# top_schem_rev10_3.net
KiCad netlist of a schematic drawn in Altium Designer
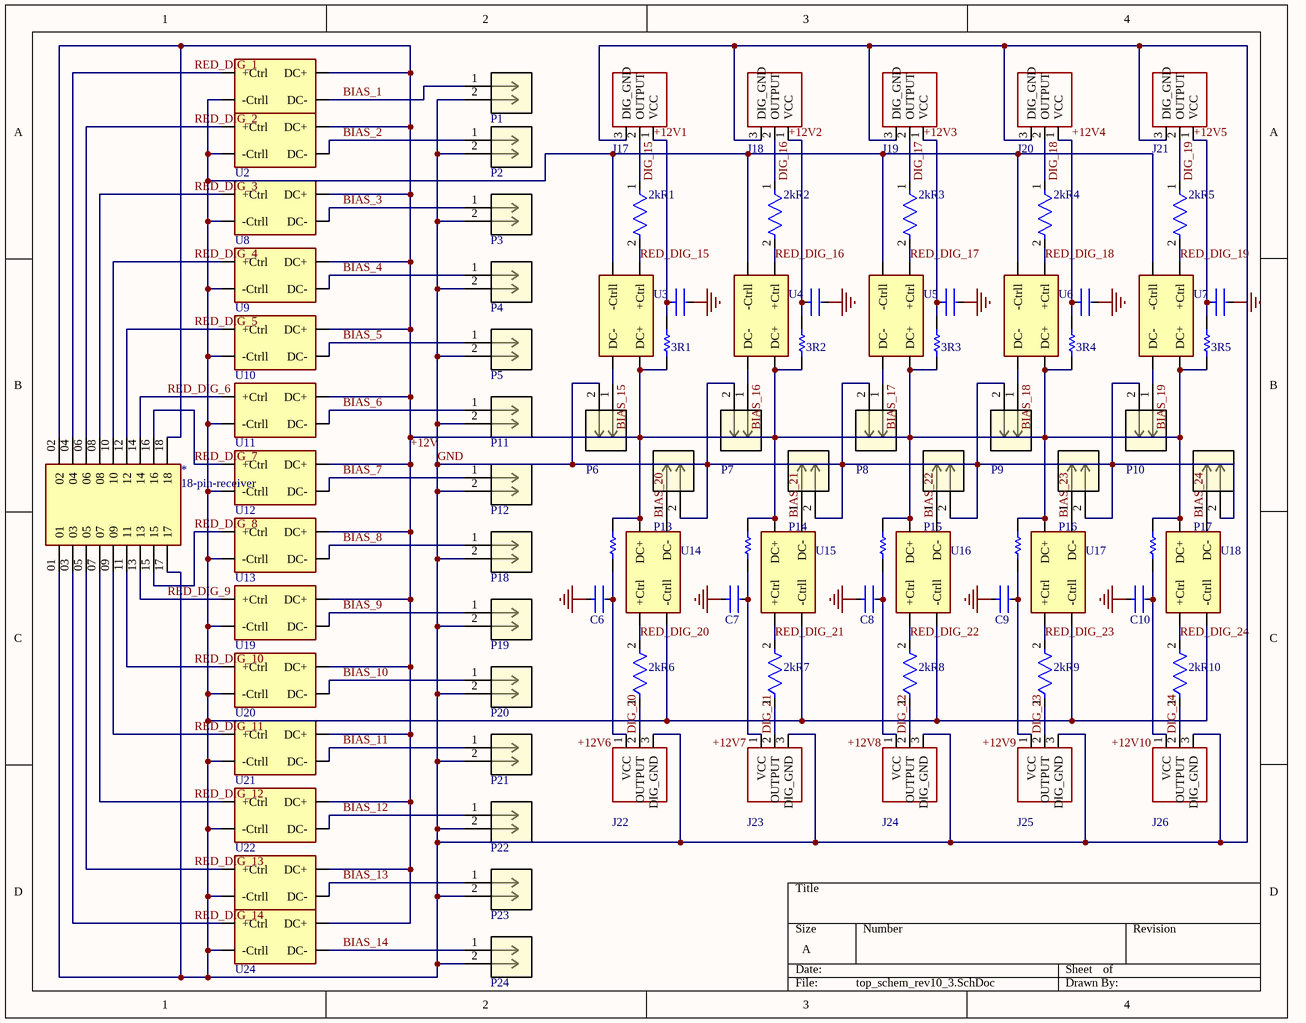
[diagram p0: top_schem_rev10_3.SchDoc]

(export (version "E")
  (design (tool "Eeschema 10.0.6"))
  (components
    (comp (ref "*")
      (value "18-pin-receiver")
      (footprint "18-pin-receiver")
      (libsource (lib "top_schlib") (part "18-pin-receiver"))
    )
    (comp (ref "2kR1")
      (value "CRCW06031K80FKEA")
      (footprint "2kOhm")
      (description "Res Thick Film 0603 1.8K Ohm 1% 1/10W ±100ppm/°C Molded SMD Paper T/R")
      (fields (field (name "MANUFACTURER") "Vishay") (field (name "TOLERANCE") "1%"))
      (libsource (lib "ps_schlib") (part "CRCW06031K80FKEA"))
    )
    (comp (ref "2kR2")
      (value "CRCW06031K80FKEA")
      (footprint "2kOhm")
      (description "Res Thick Film 0603 1.8K Ohm 1% 1/10W ±100ppm/°C Molded SMD Paper T/R")
      (fields (field (name "MANUFACTURER") "Vishay") (field (name "TOLERANCE") "1%"))
      (libsource (lib "ps_schlib") (part "CRCW06031K80FKEA"))
    )
    (comp (ref "2kR3")
      (value "CRCW06031K80FKEA")
      (footprint "2kOhm")
      (description "Res Thick Film 0603 1.8K Ohm 1% 1/10W ±100ppm/°C Molded SMD Paper T/R")
      (fields (field (name "MANUFACTURER") "Vishay") (field (name "TOLERANCE") "1%"))
      (libsource (lib "ps_schlib") (part "CRCW06031K80FKEA"))
    )
    (comp (ref "2kR4")
      (value "CRCW06031K80FKEA")
      (footprint "2kOhm")
      (description "Res Thick Film 0603 1.8K Ohm 1% 1/10W ±100ppm/°C Molded SMD Paper T/R")
      (fields (field (name "MANUFACTURER") "Vishay") (field (name "TOLERANCE") "1%"))
      (libsource (lib "ps_schlib") (part "CRCW06031K80FKEA"))
    )
    (comp (ref "2kR5")
      (value "CRCW06031K80FKEA")
      (footprint "2kOhm")
      (description "Res Thick Film 0603 1.8K Ohm 1% 1/10W ±100ppm/°C Molded SMD Paper T/R")
      (fields (field (name "MANUFACTURER") "Vishay") (field (name "TOLERANCE") "1%"))
      (libsource (lib "ps_schlib") (part "CRCW06031K80FKEA"))
    )
    (comp (ref "2kR6")
      (value "CRCW06031K80FKEA")
      (footprint "2kOhm")
      (description "Res Thick Film 0603 1.8K Ohm 1% 1/10W ±100ppm/°C Molded SMD Paper T/R")
      (fields (field (name "MANUFACTURER") "Vishay") (field (name "TOLERANCE") "1%"))
      (libsource (lib "ps_schlib") (part "CRCW06031K80FKEA"))
    )
    (comp (ref "2kR7")
      (value "CRCW06031K80FKEA")
      (footprint "2kOhm")
      (description "Res Thick Film 0603 1.8K Ohm 1% 1/10W ±100ppm/°C Molded SMD Paper T/R")
      (fields (field (name "MANUFACTURER") "Vishay") (field (name "TOLERANCE") "1%"))
      (libsource (lib "ps_schlib") (part "CRCW06031K80FKEA"))
    )
    (comp (ref "2kR8")
      (value "CRCW06031K80FKEA")
      (footprint "2kOhm")
      (description "Res Thick Film 0603 1.8K Ohm 1% 1/10W ±100ppm/°C Molded SMD Paper T/R")
      (fields (field (name "MANUFACTURER") "Vishay") (field (name "TOLERANCE") "1%"))
      (libsource (lib "ps_schlib") (part "CRCW06031K80FKEA"))
    )
    (comp (ref "2kR9")
      (value "CRCW06031K80FKEA")
      (footprint "2kOhm")
      (description "Res Thick Film 0603 1.8K Ohm 1% 1/10W ±100ppm/°C Molded SMD Paper T/R")
      (fields (field (name "MANUFACTURER") "Vishay") (field (name "TOLERANCE") "1%"))
      (libsource (lib "ps_schlib") (part "CRCW06031K80FKEA"))
    )
    (comp (ref "2kR10")
      (value "CRCW06031K80FKEA")
      (footprint "2kOhm")
      (description "Res Thick Film 0603 1.8K Ohm 1% 1/10W ±100ppm/°C Molded SMD Paper T/R")
      (fields (field (name "MANUFACTURER") "Vishay") (field (name "TOLERANCE") "1%"))
      (libsource (lib "ps_schlib") (part "CRCW06031K80FKEA"))
    )
    (comp (ref "3R1")
      (value "ERJ-2BQJR30X")
      (footprint "03 Ohm")
      (description "RES 0.3 OHM 5% 1/6W 0402")
      (fields (field (name "MANUFACTURER") "Panasonic") (field (name "TOLERANCE") "5%"))
      (libsource (lib "ps_schlib") (part "ERJ-2BQJR30X"))
    )
    (comp (ref "3R2")
      (value "ERJ-2BQJR30X")
      (footprint "03 Ohm")
      (description "RES 0.3 OHM 5% 1/6W 0402")
      (fields (field (name "MANUFACTURER") "Panasonic") (field (name "TOLERANCE") "5%"))
      (libsource (lib "ps_schlib") (part "ERJ-2BQJR30X"))
    )
    (comp (ref "3R3")
      (value "ERJ-2BQJR30X")
      (footprint "03 Ohm")
      (description "RES 0.3 OHM 5% 1/6W 0402")
      (fields (field (name "MANUFACTURER") "Panasonic") (field (name "TOLERANCE") "5%"))
      (libsource (lib "ps_schlib") (part "ERJ-2BQJR30X"))
    )
    (comp (ref "3R4")
      (value "ERJ-2BQJR30X")
      (footprint "03 Ohm")
      (description "RES 0.3 OHM 5% 1/6W 0402")
      (fields (field (name "MANUFACTURER") "Panasonic") (field (name "TOLERANCE") "5%"))
      (libsource (lib "ps_schlib") (part "ERJ-2BQJR30X"))
    )
    (comp (ref "3R5")
      (value "ERJ-2BQJR30X")
      (footprint "03 Ohm")
      (description "RES 0.3 OHM 5% 1/6W 0402")
      (fields (field (name "MANUFACTURER") "Panasonic") (field (name "TOLERANCE") "5%"))
      (libsource (lib "ps_schlib") (part "ERJ-2BQJR30X"))
    )
    (comp (ref "3R6")
      (value "ERJ-2BQJR30X")
      (footprint "03 Ohm")
      (description "RES 0.3 OHM 5% 1/6W 0402")
      (fields (field (name "MANUFACTURER") "Panasonic") (field (name "TOLERANCE") "5%"))
      (libsource (lib "ps_schlib") (part "ERJ-2BQJR30X"))
    )
    (comp (ref "3R7")
      (value "ERJ-2BQJR30X")
      (footprint "03 Ohm")
      (description "RES 0.3 OHM 5% 1/6W 0402")
      (fields (field (name "MANUFACTURER") "Panasonic") (field (name "TOLERANCE") "5%"))
      (libsource (lib "ps_schlib") (part "ERJ-2BQJR30X"))
    )
    (comp (ref "3R8")
      (value "ERJ-2BQJR30X")
      (footprint "03 Ohm")
      (description "RES 0.3 OHM 5% 1/6W 0402")
      (fields (field (name "MANUFACTURER") "Panasonic") (field (name "TOLERANCE") "5%"))
      (libsource (lib "ps_schlib") (part "ERJ-2BQJR30X"))
    )
    (comp (ref "3R9")
      (value "ERJ-2BQJR30X")
      (footprint "03 Ohm")
      (description "RES 0.3 OHM 5% 1/6W 0402")
      (fields (field (name "MANUFACTURER") "Panasonic") (field (name "TOLERANCE") "5%"))
      (libsource (lib "ps_schlib") (part "ERJ-2BQJR30X"))
    )
    (comp (ref "3R10")
      (value "ERJ-2BQJR30X")
      (footprint "03 Ohm")
      (description "RES 0.3 OHM 5% 1/6W 0402")
      (fields (field (name "MANUFACTURER") "Panasonic") (field (name "TOLERANCE") "5%"))
      (libsource (lib "ps_schlib") (part "ERJ-2BQJR30X"))
    )
    (comp (ref "C1")
      (value "C0805C104K5RACTU")
      (footprint "100nF")
      (description "Cap Ceramic 0.1uF 50V X7R 10% SMD 2.0 x 1.2 mm 125 C Paper T/R")
      (fields (field (name "MANUFACTURER") "KEMET") (field (name "TOLERANCE") "10%"))
      (libsource (lib "ps_schlib") (part "C0805C104K5RACTU"))
    )
    (comp (ref "C2")
      (value "C0805C104K5RACTU")
      (footprint "100nF")
      (description "Cap Ceramic 0.1uF 50V X7R 10% SMD 2.0 x 1.2 mm 125 C Paper T/R")
      (fields (field (name "MANUFACTURER") "KEMET") (field (name "TOLERANCE") "10%"))
      (libsource (lib "ps_schlib") (part "C0805C104K5RACTU"))
    )
    (comp (ref "C3")
      (value "C0805C104K5RACTU")
      (footprint "100nF")
      (description "Cap Ceramic 0.1uF 50V X7R 10% SMD 2.0 x 1.2 mm 125 C Paper T/R")
      (fields (field (name "MANUFACTURER") "KEMET") (field (name "TOLERANCE") "10%"))
      (libsource (lib "ps_schlib") (part "C0805C104K5RACTU"))
    )
    (comp (ref "C4")
      (value "C0805C104K5RACTU")
      (footprint "100nF")
      (description "Cap Ceramic 0.1uF 50V X7R 10% SMD 2.0 x 1.2 mm 125 C Paper T/R")
      (fields (field (name "MANUFACTURER") "KEMET") (field (name "TOLERANCE") "10%"))
      (libsource (lib "ps_schlib") (part "C0805C104K5RACTU"))
    )
    (comp (ref "C5")
      (value "C0805C104K5RACTU")
      (footprint "100nF")
      (description "Cap Ceramic 0.1uF 50V X7R 10% SMD 2.0 x 1.2 mm 125 C Paper T/R")
      (fields (field (name "MANUFACTURER") "KEMET") (field (name "TOLERANCE") "10%"))
      (libsource (lib "ps_schlib") (part "C0805C104K5RACTU"))
    )
    (comp (ref "C6")
      (value "C0805C104K5RACTU")
      (footprint "100nF")
      (description "Cap Ceramic 0.1uF 50V X7R 10% SMD 2.0 x 1.2 mm 125 C Paper T/R")
      (fields (field (name "MANUFACTURER") "KEMET") (field (name "TOLERANCE") "10%"))
      (libsource (lib "ps_schlib") (part "C0805C104K5RACTU"))
    )
    (comp (ref "C7")
      (value "C0805C104K5RACTU")
      (footprint "100nF")
      (description "Cap Ceramic 0.1uF 50V X7R 10% SMD 2.0 x 1.2 mm 125 C Paper T/R")
      (fields (field (name "MANUFACTURER") "KEMET") (field (name "TOLERANCE") "10%"))
      (libsource (lib "ps_schlib") (part "C0805C104K5RACTU"))
    )
    (comp (ref "C8")
      (value "C0805C104K5RACTU")
      (footprint "100nF")
      (description "Cap Ceramic 0.1uF 50V X7R 10% SMD 2.0 x 1.2 mm 125 C Paper T/R")
      (fields (field (name "MANUFACTURER") "KEMET") (field (name "TOLERANCE") "10%"))
      (libsource (lib "ps_schlib") (part "C0805C104K5RACTU"))
    )
    (comp (ref "C9")
      (value "C0805C104K5RACTU")
      (footprint "100nF")
      (description "Cap Ceramic 0.1uF 50V X7R 10% SMD 2.0 x 1.2 mm 125 C Paper T/R")
      (fields (field (name "MANUFACTURER") "KEMET") (field (name "TOLERANCE") "10%"))
      (libsource (lib "ps_schlib") (part "C0805C104K5RACTU"))
    )
    (comp (ref "C10")
      (value "C0805C104K5RACTU")
      (footprint "100nF")
      (description "Cap Ceramic 0.1uF 50V X7R 10% SMD 2.0 x 1.2 mm 125 C Paper T/R")
      (fields (field (name "MANUFACTURER") "KEMET") (field (name "TOLERANCE") "10%"))
      (libsource (lib "ps_schlib") (part "C0805C104K5RACTU"))
    )
    (comp (ref "J17")
      (value "IF-D95T")
      (footprint "IF-D95")
      (description "DETECTOR PHOTOLOGIC TTL/CMOS")
      (fields (field (name "MANUFACTURER") "Industrial Fiber Optics"))
      (libsource (lib "ps_schlib") (part "IF-D95T"))
    )
    (comp (ref "J18")
      (value "IF-D95T")
      (footprint "IF-D95")
      (description "DETECTOR PHOTOLOGIC TTL/CMOS")
      (fields (field (name "MANUFACTURER") "Industrial Fiber Optics"))
      (libsource (lib "ps_schlib") (part "IF-D95T"))
    )
    (comp (ref "J19")
      (value "IF-D95T")
      (footprint "IF-D95")
      (description "DETECTOR PHOTOLOGIC TTL/CMOS")
      (fields (field (name "MANUFACTURER") "Industrial Fiber Optics"))
      (libsource (lib "ps_schlib") (part "IF-D95T"))
    )
    (comp (ref "J20")
      (value "IF-D95T")
      (footprint "IF-D95")
      (description "DETECTOR PHOTOLOGIC TTL/CMOS")
      (fields (field (name "MANUFACTURER") "Industrial Fiber Optics"))
      (libsource (lib "ps_schlib") (part "IF-D95T"))
    )
    (comp (ref "J21")
      (value "IF-D95T")
      (footprint "IF-D95")
      (description "DETECTOR PHOTOLOGIC TTL/CMOS")
      (fields (field (name "MANUFACTURER") "Industrial Fiber Optics"))
      (libsource (lib "ps_schlib") (part "IF-D95T"))
    )
    (comp (ref "J22")
      (value "IF-D95T")
      (footprint "IF-D95")
      (description "DETECTOR PHOTOLOGIC TTL/CMOS")
      (fields (field (name "MANUFACTURER") "Industrial Fiber Optics"))
      (libsource (lib "ps_schlib") (part "IF-D95T"))
    )
    (comp (ref "J23")
      (value "IF-D95T")
      (footprint "IF-D95")
      (description "DETECTOR PHOTOLOGIC TTL/CMOS")
      (fields (field (name "MANUFACTURER") "Industrial Fiber Optics"))
      (libsource (lib "ps_schlib") (part "IF-D95T"))
    )
    (comp (ref "J24")
      (value "IF-D95T")
      (footprint "IF-D95")
      (description "DETECTOR PHOTOLOGIC TTL/CMOS")
      (fields (field (name "MANUFACTURER") "Industrial Fiber Optics"))
      (libsource (lib "ps_schlib") (part "IF-D95T"))
    )
    (comp (ref "J25")
      (value "IF-D95T")
      (footprint "IF-D95")
      (description "DETECTOR PHOTOLOGIC TTL/CMOS")
      (fields (field (name "MANUFACTURER") "Industrial Fiber Optics"))
      (libsource (lib "ps_schlib") (part "IF-D95T"))
    )
    (comp (ref "J26")
      (value "IF-D95T")
      (footprint "IF-D95")
      (description "DETECTOR PHOTOLOGIC TTL/CMOS")
      (fields (field (name "MANUFACTURER") "Industrial Fiber Optics"))
      (libsource (lib "ps_schlib") (part "IF-D95T"))
    )
    (comp (ref "P1")
      (value "1054311102")
      (footprint "CONN_1054311102_MOL")
      (fields (field (name "MANUFACTURER") "Molex"))
      (libsource (lib "") (part "1054311102_1"))
    )
    (comp (ref "P2")
      (value "1054311102")
      (footprint "CONN_1054311102_MOL")
      (fields (field (name "MANUFACTURER") "Molex"))
      (libsource (lib "") (part "1054311102_1"))
    )
    (comp (ref "P3")
      (value "1054311102")
      (footprint "CONN_1054311102_MOL")
      (fields (field (name "MANUFACTURER") "Molex"))
      (libsource (lib "") (part "1054311102_1"))
    )
    (comp (ref "P4")
      (value "1054311102")
      (footprint "CONN_1054311102_MOL")
      (fields (field (name "MANUFACTURER") "Molex"))
      (libsource (lib "") (part "1054311102_1"))
    )
    (comp (ref "P5")
      (value "1054311102")
      (footprint "CONN_1054311102_MOL")
      (fields (field (name "MANUFACTURER") "Molex"))
      (libsource (lib "") (part "1054311102_1"))
    )
    (comp (ref "P6")
      (value "1054311102")
      (footprint "CONN_1054311102_MOL")
      (fields (field (name "MANUFACTURER") "Molex"))
      (libsource (lib "") (part "1054311102_2"))
    )
    (comp (ref "P7")
      (value "1054311102")
      (footprint "CONN_1054311102_MOL")
      (fields (field (name "MANUFACTURER") "Molex"))
      (libsource (lib "") (part "1054311102_2"))
    )
    (comp (ref "P8")
      (value "1054311102")
      (footprint "CONN_1054311102_MOL")
      (fields (field (name "MANUFACTURER") "Molex"))
      (libsource (lib "") (part "1054311102_2"))
    )
    (comp (ref "P9")
      (value "1054311102")
      (footprint "CONN_1054311102_MOL")
      (fields (field (name "MANUFACTURER") "Molex"))
      (libsource (lib "") (part "1054311102_2"))
    )
    (comp (ref "P10")
      (value "1054311102")
      (footprint "CONN_1054311102_MOL")
      (fields (field (name "MANUFACTURER") "Molex"))
      (libsource (lib "") (part "1054311102_2"))
    )
    (comp (ref "P11")
      (value "1054311102")
      (footprint "CONN_1054311102_MOL")
      (fields (field (name "MANUFACTURER") "Molex"))
      (libsource (lib "") (part "1054311102_1"))
    )
    (comp (ref "P12")
      (value "1054311102")
      (footprint "CONN_1054311102_MOL")
      (fields (field (name "MANUFACTURER") "Molex"))
      (libsource (lib "") (part "1054311102_1"))
    )
    (comp (ref "P13")
      (value "1054311102")
      (footprint "CONN_1054311102_MOL")
      (fields (field (name "MANUFACTURER") "Molex"))
      (libsource (lib "ps_schlib") (part "1054311102"))
    )
    (comp (ref "P14")
      (value "1054311102")
      (footprint "CONN_1054311102_MOL")
      (fields (field (name "MANUFACTURER") "Molex"))
      (libsource (lib "ps_schlib") (part "1054311102"))
    )
    (comp (ref "P15")
      (value "1054311102")
      (footprint "CONN_1054311102_MOL")
      (fields (field (name "MANUFACTURER") "Molex"))
      (libsource (lib "ps_schlib") (part "1054311102"))
    )
    (comp (ref "P16")
      (value "1054311102")
      (footprint "CONN_1054311102_MOL")
      (fields (field (name "MANUFACTURER") "Molex"))
      (libsource (lib "ps_schlib") (part "1054311102"))
    )
    (comp (ref "P17")
      (value "1054311102")
      (footprint "CONN_1054311102_MOL")
      (fields (field (name "MANUFACTURER") "Molex"))
      (libsource (lib "ps_schlib") (part "1054311102"))
    )
    (comp (ref "P18")
      (value "1054311102")
      (footprint "CONN_1054311102_MOL")
      (fields (field (name "MANUFACTURER") "Molex"))
      (libsource (lib "") (part "1054311102_1"))
    )
    (comp (ref "P19")
      (value "1054311102")
      (footprint "CONN_1054311102_MOL")
      (fields (field (name "MANUFACTURER") "Molex"))
      (libsource (lib "") (part "1054311102_1"))
    )
    (comp (ref "P20")
      (value "1054311102")
      (footprint "CONN_1054311102_MOL")
      (fields (field (name "MANUFACTURER") "Molex"))
      (libsource (lib "") (part "1054311102_1"))
    )
    (comp (ref "P21")
      (value "1054311102")
      (footprint "CONN_1054311102_MOL")
      (fields (field (name "MANUFACTURER") "Molex"))
      (libsource (lib "") (part "1054311102_1"))
    )
    (comp (ref "P22")
      (value "1054311102")
      (footprint "CONN_1054311102_MOL")
      (fields (field (name "MANUFACTURER") "Molex"))
      (libsource (lib "") (part "1054311102_1"))
    )
    (comp (ref "P23")
      (value "1054311102")
      (footprint "CONN_1054311102_MOL")
      (fields (field (name "MANUFACTURER") "Molex"))
      (libsource (lib "") (part "1054311102_1"))
    )
    (comp (ref "P24")
      (value "1054311102")
      (footprint "CONN_1054311102_MOL")
      (fields (field (name "MANUFACTURER") "Molex"))
      (libsource (lib "") (part "1054311102_1"))
    )
    (comp (ref "U1")
      (value "Solid state relay")
      (footprint "CPC1002N")
      (libsource (lib "") (part "CPC1002N_1"))
    )
    (comp (ref "U2")
      (value "Solid state relay")
      (footprint "CPC1002N")
      (libsource (lib "") (part "CPC1002N_1"))
    )
    (comp (ref "U3")
      (value "Solid state relay")
      (footprint "CPC1002N")
      (libsource (lib "ps_schlib") (part "CPC1002N"))
    )
    (comp (ref "U4")
      (value "Solid state relay")
      (footprint "CPC1002N")
      (libsource (lib "ps_schlib") (part "CPC1002N"))
    )
    (comp (ref "U5")
      (value "Solid state relay")
      (footprint "CPC1002N")
      (libsource (lib "ps_schlib") (part "CPC1002N"))
    )
    (comp (ref "U6")
      (value "Solid state relay")
      (footprint "CPC1002N")
      (libsource (lib "ps_schlib") (part "CPC1002N"))
    )
    (comp (ref "U7")
      (value "Solid state relay")
      (footprint "CPC1002N")
      (libsource (lib "ps_schlib") (part "CPC1002N"))
    )
    (comp (ref "U8")
      (value "Solid state relay")
      (footprint "CPC1002N")
      (libsource (lib "") (part "CPC1002N_1"))
    )
    (comp (ref "U9")
      (value "Solid state relay")
      (footprint "CPC1002N")
      (libsource (lib "") (part "CPC1002N_1"))
    )
    (comp (ref "U10")
      (value "Solid state relay")
      (footprint "CPC1002N")
      (libsource (lib "") (part "CPC1002N_1"))
    )
    (comp (ref "U11")
      (value "Solid state relay")
      (footprint "CPC1002N")
      (libsource (lib "") (part "CPC1002N_1"))
    )
    (comp (ref "U12")
      (value "Solid state relay")
      (footprint "CPC1002N")
      (libsource (lib "") (part "CPC1002N_1"))
    )
    (comp (ref "U13")
      (value "Solid state relay")
      (footprint "CPC1002N")
      (libsource (lib "") (part "CPC1002N_1"))
    )
    (comp (ref "U14")
      (value "Solid state relay")
      (footprint "CPC1002N")
      (libsource (lib "") (part "CPC1002N_2"))
    )
    (comp (ref "U15")
      (value "Solid state relay")
      (footprint "CPC1002N")
      (libsource (lib "") (part "CPC1002N_2"))
    )
    (comp (ref "U16")
      (value "Solid state relay")
      (footprint "CPC1002N")
      (libsource (lib "") (part "CPC1002N_2"))
    )
    (comp (ref "U17")
      (value "Solid state relay")
      (footprint "CPC1002N")
      (libsource (lib "") (part "CPC1002N_2"))
    )
    (comp (ref "U18")
      (value "Solid state relay")
      (footprint "CPC1002N")
      (libsource (lib "") (part "CPC1002N_2"))
    )
    (comp (ref "U19")
      (value "Solid state relay")
      (footprint "CPC1002N")
      (libsource (lib "") (part "CPC1002N_1"))
    )
    (comp (ref "U20")
      (value "Solid state relay")
      (footprint "CPC1002N")
      (libsource (lib "") (part "CPC1002N_1"))
    )
    (comp (ref "U21")
      (value "Solid state relay")
      (footprint "CPC1002N")
      (libsource (lib "") (part "CPC1002N_1"))
    )
    (comp (ref "U22")
      (value "Solid state relay")
      (footprint "CPC1002N")
      (libsource (lib "") (part "CPC1002N_1"))
    )
    (comp (ref "U23")
      (value "Solid state relay")
      (footprint "CPC1002N")
      (libsource (lib "") (part "CPC1002N_1"))
    )
    (comp (ref "U24")
      (value "Solid state relay")
      (footprint "CPC1002N")
      (libsource (lib "") (part "CPC1002N_1"))
    )
  )
  (nets
    (net (code "1") (name "/+12V") (class "Default")
      (node (ref "*") (pin "02") (pinfunction "02_02") (pintype "passive"))
      (node (ref "*") (pin "18") (pinfunction "18_18") (pintype "passive"))
      (node (ref "3R1") (pin "1") (pinfunction "1_1") (pintype "passive"))
      (node (ref "3R10") (pin "2") (pinfunction "2_2") (pintype "passive"))
      (node (ref "3R2") (pin "1") (pinfunction "1_1") (pintype "passive"))
      (node (ref "3R3") (pin "1") (pinfunction "1_1") (pintype "passive"))
      (node (ref "3R4") (pin "1") (pinfunction "1_1") (pintype "passive"))
      (node (ref "3R5") (pin "1") (pinfunction "1_1") (pintype "passive"))
      (node (ref "3R6") (pin "2") (pinfunction "2_2") (pintype "passive"))
      (node (ref "3R7") (pin "2") (pinfunction "2_2") (pintype "passive"))
      (node (ref "3R8") (pin "2") (pinfunction "2_2") (pintype "passive"))
      (node (ref "3R9") (pin "2") (pinfunction "2_2") (pintype "passive"))
      (node (ref "U1") (pin "4") (pinfunction "DC+_4") (pintype "passive"))
      (node (ref "U10") (pin "4") (pinfunction "DC+_4") (pintype "passive"))
      (node (ref "U11") (pin "4") (pinfunction "DC+_4") (pintype "passive"))
      (node (ref "U12") (pin "4") (pinfunction "DC+_4") (pintype "passive"))
      (node (ref "U13") (pin "4") (pinfunction "DC+_4") (pintype "passive"))
      (node (ref "U14") (pin "4") (pinfunction "DC+_4") (pintype "passive"))
      (node (ref "U15") (pin "4") (pinfunction "DC+_4") (pintype "passive"))
      (node (ref "U16") (pin "4") (pinfunction "DC+_4") (pintype "passive"))
      (node (ref "U17") (pin "4") (pinfunction "DC+_4") (pintype "passive"))
      (node (ref "U18") (pin "4") (pinfunction "DC+_4") (pintype "passive"))
      (node (ref "U19") (pin "4") (pinfunction "DC+_4") (pintype "passive"))
      (node (ref "U2") (pin "4") (pinfunction "DC+_4") (pintype "passive"))
      (node (ref "U20") (pin "4") (pinfunction "DC+_4") (pintype "passive"))
      (node (ref "U21") (pin "4") (pinfunction "DC+_4") (pintype "passive"))
      (node (ref "U22") (pin "4") (pinfunction "DC+_4") (pintype "passive"))
      (node (ref "U23") (pin "4") (pinfunction "DC+_4") (pintype "passive"))
      (node (ref "U24") (pin "4") (pinfunction "DC+_4") (pintype "passive"))
      (node (ref "U3") (pin "4") (pinfunction "DC+_4") (pintype "passive"))
      (node (ref "U4") (pin "4") (pinfunction "DC+_4") (pintype "passive"))
      (node (ref "U5") (pin "4") (pinfunction "DC+_4") (pintype "passive"))
      (node (ref "U6") (pin "4") (pinfunction "DC+_4") (pintype "passive"))
      (node (ref "U7") (pin "4") (pinfunction "DC+_4") (pintype "passive"))
      (node (ref "U8") (pin "4") (pinfunction "DC+_4") (pintype "passive"))
      (node (ref "U9") (pin "4") (pinfunction "DC+_4") (pintype "passive"))
    )
    (net (code "2") (name "/+12V1") (class "Default")
      (node (ref "3R1") (pin "2") (pinfunction "2_2") (pintype "passive"))
      (node (ref "C1") (pin "1") (pinfunction "1_1") (pintype "passive"))
      (node (ref "J17") (pin "1") (pinfunction "VCC_1") (pintype "passive"))
    )
    (net (code "3") (name "/+12V2") (class "Default")
      (node (ref "3R2") (pin "2") (pinfunction "2_2") (pintype "passive"))
      (node (ref "C2") (pin "1") (pinfunction "1_1") (pintype "passive"))
      (node (ref "J18") (pin "1") (pinfunction "VCC_1") (pintype "passive"))
    )
    (net (code "4") (name "/+12V3") (class "Default")
      (node (ref "3R3") (pin "2") (pinfunction "2_2") (pintype "passive"))
      (node (ref "C3") (pin "1") (pinfunction "1_1") (pintype "passive"))
      (node (ref "J19") (pin "1") (pinfunction "VCC_1") (pintype "passive"))
    )
    (net (code "5") (name "/+12V4") (class "Default")
      (node (ref "3R4") (pin "2") (pinfunction "2_2") (pintype "passive"))
      (node (ref "C4") (pin "1") (pinfunction "1_1") (pintype "passive"))
      (node (ref "J20") (pin "1") (pinfunction "VCC_1") (pintype "passive"))
    )
    (net (code "6") (name "/+12V5") (class "Default")
      (node (ref "3R5") (pin "2") (pinfunction "2_2") (pintype "passive"))
      (node (ref "C5") (pin "1") (pinfunction "1_1") (pintype "passive"))
      (node (ref "J21") (pin "1") (pinfunction "VCC_1") (pintype "passive"))
    )
    (net (code "7") (name "/+12V6") (class "Default")
      (node (ref "3R6") (pin "1") (pinfunction "1_1") (pintype "passive"))
      (node (ref "C6") (pin "2") (pinfunction "2_2") (pintype "passive"))
      (node (ref "J22") (pin "1") (pinfunction "VCC_1") (pintype "passive"))
    )
    (net (code "8") (name "/+12V7") (class "Default")
      (node (ref "3R7") (pin "1") (pinfunction "1_1") (pintype "passive"))
      (node (ref "C7") (pin "2") (pinfunction "2_2") (pintype "passive"))
      (node (ref "J23") (pin "1") (pinfunction "VCC_1") (pintype "passive"))
    )
    (net (code "9") (name "/+12V8") (class "Default")
      (node (ref "3R8") (pin "1") (pinfunction "1_1") (pintype "passive"))
      (node (ref "C8") (pin "2") (pinfunction "2_2") (pintype "passive"))
      (node (ref "J24") (pin "1") (pinfunction "VCC_1") (pintype "passive"))
    )
    (net (code "10") (name "/+12V9") (class "Default")
      (node (ref "3R9") (pin "1") (pinfunction "1_1") (pintype "passive"))
      (node (ref "C9") (pin "2") (pinfunction "2_2") (pintype "passive"))
      (node (ref "J25") (pin "1") (pinfunction "VCC_1") (pintype "passive"))
    )
    (net (code "11") (name "/+12V10") (class "Default")
      (node (ref "3R10") (pin "1") (pinfunction "1_1") (pintype "passive"))
      (node (ref "C10") (pin "2") (pinfunction "2_2") (pintype "passive"))
      (node (ref "J26") (pin "1") (pinfunction "VCC_1") (pintype "passive"))
    )
    (net (code "12") (name "/BIAS_1") (class "Default")
      (node (ref "P1") (pin "1") (pinfunction "1_1") (pintype "passive"))
      (node (ref "U1") (pin "3") (pinfunction "DC-_3") (pintype "passive"))
    )
    (net (code "13") (name "/BIAS_2") (class "Default")
      (node (ref "P2") (pin "1") (pinfunction "1_1") (pintype "passive"))
      (node (ref "U2") (pin "3") (pinfunction "DC-_3") (pintype "passive"))
    )
    (net (code "14") (name "/BIAS_3") (class "Default")
      (node (ref "P3") (pin "1") (pinfunction "1_1") (pintype "passive"))
      (node (ref "U8") (pin "3") (pinfunction "DC-_3") (pintype "passive"))
    )
    (net (code "15") (name "/BIAS_4") (class "Default")
      (node (ref "P4") (pin "1") (pinfunction "1_1") (pintype "passive"))
      (node (ref "U9") (pin "3") (pinfunction "DC-_3") (pintype "passive"))
    )
    (net (code "16") (name "/BIAS_5") (class "Default")
      (node (ref "P5") (pin "1") (pinfunction "1_1") (pintype "passive"))
      (node (ref "U10") (pin "3") (pinfunction "DC-_3") (pintype "passive"))
    )
    (net (code "17") (name "/BIAS_6") (class "Default")
      (node (ref "P11") (pin "1") (pinfunction "1_1") (pintype "passive"))
      (node (ref "U11") (pin "3") (pinfunction "DC-_3") (pintype "passive"))
    )
    (net (code "18") (name "/BIAS_7") (class "Default")
      (node (ref "P12") (pin "1") (pinfunction "1_1") (pintype "passive"))
      (node (ref "U12") (pin "3") (pinfunction "DC-_3") (pintype "passive"))
    )
    (net (code "19") (name "/BIAS_8") (class "Default")
      (node (ref "P18") (pin "1") (pinfunction "1_1") (pintype "passive"))
      (node (ref "U13") (pin "3") (pinfunction "DC-_3") (pintype "passive"))
    )
    (net (code "20") (name "/BIAS_9") (class "Default")
      (node (ref "P19") (pin "1") (pinfunction "1_1") (pintype "passive"))
      (node (ref "U19") (pin "3") (pinfunction "DC-_3") (pintype "passive"))
    )
    (net (code "21") (name "/BIAS_10") (class "Default")
      (node (ref "P20") (pin "1") (pinfunction "1_1") (pintype "passive"))
      (node (ref "U20") (pin "3") (pinfunction "DC-_3") (pintype "passive"))
    )
    (net (code "22") (name "/BIAS_11") (class "Default")
      (node (ref "P21") (pin "1") (pinfunction "1_1") (pintype "passive"))
      (node (ref "U21") (pin "3") (pinfunction "DC-_3") (pintype "passive"))
    )
    (net (code "23") (name "/BIAS_12") (class "Default")
      (node (ref "P22") (pin "1") (pinfunction "1_1") (pintype "passive"))
      (node (ref "U22") (pin "3") (pinfunction "DC-_3") (pintype "passive"))
    )
    (net (code "24") (name "/BIAS_13") (class "Default")
      (node (ref "P23") (pin "1") (pinfunction "1_1") (pintype "passive"))
      (node (ref "U23") (pin "3") (pinfunction "DC-_3") (pintype "passive"))
    )
    (net (code "25") (name "/BIAS_14") (class "Default")
      (node (ref "P24") (pin "1") (pinfunction "1_1") (pintype "passive"))
      (node (ref "U24") (pin "3") (pinfunction "DC-_3") (pintype "passive"))
    )
    (net (code "26") (name "/BIAS_15") (class "Default")
      (node (ref "P6") (pin "1") (pinfunction "1_1") (pintype "passive"))
      (node (ref "U3") (pin "3") (pinfunction "DC-_3") (pintype "passive"))
    )
    (net (code "27") (name "/BIAS_16") (class "Default")
      (node (ref "P7") (pin "1") (pinfunction "1_1") (pintype "passive"))
      (node (ref "U4") (pin "3") (pinfunction "DC-_3") (pintype "passive"))
    )
    (net (code "28") (name "/BIAS_17") (class "Default")
      (node (ref "P8") (pin "1") (pinfunction "1_1") (pintype "passive"))
      (node (ref "U5") (pin "3") (pinfunction "DC-_3") (pintype "passive"))
    )
    (net (code "29") (name "/BIAS_18") (class "Default")
      (node (ref "P9") (pin "1") (pinfunction "1_1") (pintype "passive"))
      (node (ref "U6") (pin "3") (pinfunction "DC-_3") (pintype "passive"))
    )
    (net (code "30") (name "/BIAS_19") (class "Default")
      (node (ref "P10") (pin "1") (pinfunction "1_1") (pintype "passive"))
      (node (ref "U7") (pin "3") (pinfunction "DC-_3") (pintype "passive"))
    )
    (net (code "31") (name "/BIAS_20") (class "Default")
      (node (ref "P13") (pin "1") (pinfunction "1_1") (pintype "passive"))
      (node (ref "U14") (pin "3") (pinfunction "DC-_3") (pintype "passive"))
    )
    (net (code "32") (name "/BIAS_21") (class "Default")
      (node (ref "P14") (pin "1") (pinfunction "1_1") (pintype "passive"))
      (node (ref "U15") (pin "3") (pinfunction "DC-_3") (pintype "passive"))
    )
    (net (code "33") (name "/BIAS_22") (class "Default")
      (node (ref "P15") (pin "1") (pinfunction "1_1") (pintype "passive"))
      (node (ref "U16") (pin "3") (pinfunction "DC-_3") (pintype "passive"))
    )
    (net (code "34") (name "/BIAS_23") (class "Default")
      (node (ref "P16") (pin "1") (pinfunction "1_1") (pintype "passive"))
      (node (ref "U17") (pin "3") (pinfunction "DC-_3") (pintype "passive"))
    )
    (net (code "35") (name "/BIAS_24") (class "Default")
      (node (ref "P17") (pin "1") (pinfunction "1_1") (pintype "passive"))
      (node (ref "U18") (pin "3") (pinfunction "DC-_3") (pintype "passive"))
    )
    (net (code "36") (name "/DIG_15") (class "Default")
      (node (ref "2kR1") (pin "1") (pinfunction "1_1") (pintype "passive"))
      (node (ref "J17") (pin "2") (pinfunction "OUTPUT_2") (pintype "passive"))
    )
    (net (code "37") (name "/DIG_16") (class "Default")
      (node (ref "2kR2") (pin "1") (pinfunction "1_1") (pintype "passive"))
      (node (ref "J18") (pin "2") (pinfunction "OUTPUT_2") (pintype "passive"))
    )
    (net (code "38") (name "/DIG_17") (class "Default")
      (node (ref "2kR3") (pin "1") (pinfunction "1_1") (pintype "passive"))
      (node (ref "J19") (pin "2") (pinfunction "OUTPUT_2") (pintype "passive"))
    )
    (net (code "39") (name "/DIG_18") (class "Default")
      (node (ref "2kR4") (pin "1") (pinfunction "1_1") (pintype "passive"))
      (node (ref "J20") (pin "2") (pinfunction "OUTPUT_2") (pintype "passive"))
    )
    (net (code "40") (name "/DIG_19") (class "Default")
      (node (ref "2kR5") (pin "1") (pinfunction "1_1") (pintype "passive"))
      (node (ref "J21") (pin "2") (pinfunction "OUTPUT_2") (pintype "passive"))
    )
    (net (code "41") (name "/DIG_20") (class "Default")
      (node (ref "2kR6") (pin "1") (pinfunction "1_1") (pintype "passive"))
      (node (ref "J22") (pin "2") (pinfunction "OUTPUT_2") (pintype "passive"))
    )
    (net (code "42") (name "/DIG_21") (class "Default")
      (node (ref "2kR7") (pin "1") (pinfunction "1_1") (pintype "passive"))
      (node (ref "J23") (pin "2") (pinfunction "OUTPUT_2") (pintype "passive"))
    )
    (net (code "43") (name "/DIG_22") (class "Default")
      (node (ref "2kR8") (pin "1") (pinfunction "1_1") (pintype "passive"))
      (node (ref "J24") (pin "2") (pinfunction "OUTPUT_2") (pintype "passive"))
    )
    (net (code "44") (name "/DIG_23") (class "Default")
      (node (ref "2kR9") (pin "1") (pinfunction "1_1") (pintype "passive"))
      (node (ref "J25") (pin "2") (pinfunction "OUTPUT_2") (pintype "passive"))
    )
    (net (code "45") (name "/DIG_24") (class "Default")
      (node (ref "2kR10") (pin "1") (pinfunction "1_1") (pintype "passive"))
      (node (ref "J26") (pin "2") (pinfunction "OUTPUT_2") (pintype "passive"))
    )
    (net (code "46") (name "/RED_DIG_1") (class "Default")
      (node (ref "*") (pin "04") (pinfunction "04_04") (pintype "passive"))
      (node (ref "U1") (pin "1") (pinfunction "+Ctrl_1") (pintype "passive"))
    )
    (net (code "47") (name "/RED_DIG_2") (class "Default")
      (node (ref "*") (pin "06") (pinfunction "06_06") (pintype "passive"))
      (node (ref "U2") (pin "1") (pinfunction "+Ctrl_1") (pintype "passive"))
    )
    (net (code "48") (name "/RED_DIG_3") (class "Default")
      (node (ref "*") (pin "08") (pinfunction "08_08") (pintype "passive"))
      (node (ref "U8") (pin "1") (pinfunction "+Ctrl_1") (pintype "passive"))
    )
    (net (code "49") (name "/RED_DIG_4") (class "Default")
      (node (ref "*") (pin "10") (pinfunction "10_10") (pintype "passive"))
      (node (ref "U9") (pin "1") (pinfunction "+Ctrl_1") (pintype "passive"))
    )
    (net (code "50") (name "/RED_DIG_5") (class "Default")
      (node (ref "*") (pin "12") (pinfunction "12_12") (pintype "passive"))
      (node (ref "U10") (pin "1") (pinfunction "+Ctrl_1") (pintype "passive"))
    )
    (net (code "51") (name "/RED_DIG_6") (class "Default")
      (node (ref "*") (pin "14") (pinfunction "14_14") (pintype "passive"))
      (node (ref "U11") (pin "1") (pinfunction "+Ctrl_1") (pintype "passive"))
    )
    (net (code "52") (name "/RED_DIG_7") (class "Default")
      (node (ref "*") (pin "16") (pinfunction "16_16") (pintype "passive"))
      (node (ref "U12") (pin "1") (pinfunction "+Ctrl_1") (pintype "passive"))
    )
    (net (code "53") (name "/RED_DIG_8") (class "Default")
      (node (ref "*") (pin "15") (pinfunction "15_15") (pintype "passive"))
      (node (ref "U13") (pin "1") (pinfunction "+Ctrl_1") (pintype "passive"))
    )
    (net (code "54") (name "/RED_DIG_9") (class "Default")
      (node (ref "*") (pin "13") (pinfunction "13_13") (pintype "passive"))
      (node (ref "U19") (pin "1") (pinfunction "+Ctrl_1") (pintype "passive"))
    )
    (net (code "55") (name "/RED_DIG_10") (class "Default")
      (node (ref "*") (pin "11") (pinfunction "11_11") (pintype "passive"))
      (node (ref "U20") (pin "1") (pinfunction "+Ctrl_1") (pintype "passive"))
    )
    (net (code "56") (name "/RED_DIG_11") (class "Default")
      (node (ref "*") (pin "09") (pinfunction "09_09") (pintype "passive"))
      (node (ref "U21") (pin "1") (pinfunction "+Ctrl_1") (pintype "passive"))
    )
    (net (code "57") (name "/RED_DIG_12") (class "Default")
      (node (ref "*") (pin "07") (pinfunction "07_07") (pintype "passive"))
      (node (ref "U22") (pin "1") (pinfunction "+Ctrl_1") (pintype "passive"))
    )
    (net (code "58") (name "/RED_DIG_13") (class "Default")
      (node (ref "*") (pin "05") (pinfunction "05_05") (pintype "passive"))
      (node (ref "U23") (pin "1") (pinfunction "+Ctrl_1") (pintype "passive"))
    )
    (net (code "59") (name "/RED_DIG_14") (class "Default")
      (node (ref "*") (pin "03") (pinfunction "03_03") (pintype "passive"))
      (node (ref "U24") (pin "1") (pinfunction "+Ctrl_1") (pintype "passive"))
    )
    (net (code "60") (name "/RED_DIG_15") (class "Default")
      (node (ref "2kR1") (pin "2") (pinfunction "2_2") (pintype "passive"))
      (node (ref "U3") (pin "1") (pinfunction "+Ctrl_1") (pintype "passive"))
    )
    (net (code "61") (name "/RED_DIG_16") (class "Default")
      (node (ref "2kR2") (pin "2") (pinfunction "2_2") (pintype "passive"))
      (node (ref "U4") (pin "1") (pinfunction "+Ctrl_1") (pintype "passive"))
    )
    (net (code "62") (name "/RED_DIG_17") (class "Default")
      (node (ref "2kR3") (pin "2") (pinfunction "2_2") (pintype "passive"))
      (node (ref "U5") (pin "1") (pinfunction "+Ctrl_1") (pintype "passive"))
    )
    (net (code "63") (name "/RED_DIG_18") (class "Default")
      (node (ref "2kR4") (pin "2") (pinfunction "2_2") (pintype "passive"))
      (node (ref "U6") (pin "1") (pinfunction "+Ctrl_1") (pintype "passive"))
    )
    (net (code "64") (name "/RED_DIG_19") (class "Default")
      (node (ref "2kR5") (pin "2") (pinfunction "2_2") (pintype "passive"))
      (node (ref "U7") (pin "1") (pinfunction "+Ctrl_1") (pintype "passive"))
    )
    (net (code "65") (name "/RED_DIG_20") (class "Default")
      (node (ref "2kR6") (pin "2") (pinfunction "2_2") (pintype "passive"))
      (node (ref "U14") (pin "1") (pinfunction "+Ctrl_1") (pintype "passive"))
    )
    (net (code "66") (name "/RED_DIG_21") (class "Default")
      (node (ref "2kR7") (pin "2") (pinfunction "2_2") (pintype "passive"))
      (node (ref "U15") (pin "1") (pinfunction "+Ctrl_1") (pintype "passive"))
    )
    (net (code "67") (name "/RED_DIG_22") (class "Default")
      (node (ref "2kR8") (pin "2") (pinfunction "2_2") (pintype "passive"))
      (node (ref "U16") (pin "1") (pinfunction "+Ctrl_1") (pintype "passive"))
    )
    (net (code "68") (name "/RED_DIG_23") (class "Default")
      (node (ref "2kR9") (pin "2") (pinfunction "2_2") (pintype "passive"))
      (node (ref "U17") (pin "1") (pinfunction "+Ctrl_1") (pintype "passive"))
    )
    (net (code "69") (name "/RED_DIG_24") (class "Default")
      (node (ref "2kR10") (pin "2") (pinfunction "2_2") (pintype "passive"))
      (node (ref "U18") (pin "1") (pinfunction "+Ctrl_1") (pintype "passive"))
    )
    (net (code "70") (name "GND") (class "Default")
      (node (ref "*") (pin "01") (pinfunction "01_01") (pintype "passive"))
      (node (ref "*") (pin "17") (pinfunction "17_17") (pintype "passive"))
      (node (ref "C1") (pin "2") (pinfunction "2_2") (pintype "passive"))
      (node (ref "C10") (pin "1") (pinfunction "1_1") (pintype "passive"))
      (node (ref "C2") (pin "2") (pinfunction "2_2") (pintype "passive"))
      (node (ref "C3") (pin "2") (pinfunction "2_2") (pintype "passive"))
      (node (ref "C4") (pin "2") (pinfunction "2_2") (pintype "passive"))
      (node (ref "C5") (pin "2") (pinfunction "2_2") (pintype "passive"))
      (node (ref "C6") (pin "1") (pinfunction "1_1") (pintype "passive"))
      (node (ref "C7") (pin "1") (pinfunction "1_1") (pintype "passive"))
      (node (ref "C8") (pin "1") (pinfunction "1_1") (pintype "passive"))
      (node (ref "C9") (pin "1") (pinfunction "1_1") (pintype "passive"))
      (node (ref "J17") (pin "3") (pinfunction "DIG_GND_3") (pintype "passive"))
      (node (ref "J18") (pin "3") (pinfunction "DIG_GND_3") (pintype "passive"))
      (node (ref "J19") (pin "3") (pinfunction "DIG_GND_3") (pintype "passive"))
      (node (ref "J20") (pin "3") (pinfunction "DIG_GND_3") (pintype "passive"))
      (node (ref "J21") (pin "3") (pinfunction "DIG_GND_3") (pintype "passive"))
      (node (ref "J22") (pin "3") (pinfunction "DIG_GND_3") (pintype "passive"))
      (node (ref "J23") (pin "3") (pinfunction "DIG_GND_3") (pintype "passive"))
      (node (ref "J24") (pin "3") (pinfunction "DIG_GND_3") (pintype "passive"))
      (node (ref "J25") (pin "3") (pinfunction "DIG_GND_3") (pintype "passive"))
      (node (ref "J26") (pin "3") (pinfunction "DIG_GND_3") (pintype "passive"))
      (node (ref "P1") (pin "2") (pinfunction "2_2") (pintype "passive"))
      (node (ref "P10") (pin "2") (pinfunction "2_2") (pintype "passive"))
      (node (ref "P11") (pin "2") (pinfunction "2_2") (pintype "passive"))
      (node (ref "P12") (pin "2") (pinfunction "2_2") (pintype "passive"))
      (node (ref "P13") (pin "2") (pinfunction "2_2") (pintype "passive"))
      (node (ref "P14") (pin "2") (pinfunction "2_2") (pintype "passive"))
      (node (ref "P15") (pin "2") (pinfunction "2_2") (pintype "passive"))
      (node (ref "P16") (pin "2") (pinfunction "2_2") (pintype "passive"))
      (node (ref "P17") (pin "2") (pinfunction "2_2") (pintype "passive"))
      (node (ref "P18") (pin "2") (pinfunction "2_2") (pintype "passive"))
      (node (ref "P19") (pin "2") (pinfunction "2_2") (pintype "passive"))
      (node (ref "P2") (pin "2") (pinfunction "2_2") (pintype "passive"))
      (node (ref "P20") (pin "2") (pinfunction "2_2") (pintype "passive"))
      (node (ref "P21") (pin "2") (pinfunction "2_2") (pintype "passive"))
      (node (ref "P22") (pin "2") (pinfunction "2_2") (pintype "passive"))
      (node (ref "P23") (pin "2") (pinfunction "2_2") (pintype "passive"))
      (node (ref "P24") (pin "2") (pinfunction "2_2") (pintype "passive"))
      (node (ref "P3") (pin "2") (pinfunction "2_2") (pintype "passive"))
      (node (ref "P4") (pin "2") (pinfunction "2_2") (pintype "passive"))
      (node (ref "P5") (pin "2") (pinfunction "2_2") (pintype "passive"))
      (node (ref "P6") (pin "2") (pinfunction "2_2") (pintype "passive"))
      (node (ref "P7") (pin "2") (pinfunction "2_2") (pintype "passive"))
      (node (ref "P8") (pin "2") (pinfunction "2_2") (pintype "passive"))
      (node (ref "P9") (pin "2") (pinfunction "2_2") (pintype "passive"))
      (node (ref "U1") (pin "2") (pinfunction "-Ctrll_2") (pintype "passive"))
      (node (ref "U10") (pin "2") (pinfunction "-Ctrll_2") (pintype "passive"))
      (node (ref "U11") (pin "2") (pinfunction "-Ctrll_2") (pintype "passive"))
      (node (ref "U12") (pin "2") (pinfunction "-Ctrll_2") (pintype "passive"))
      (node (ref "U13") (pin "2") (pinfunction "-Ctrll_2") (pintype "passive"))
      (node (ref "U14") (pin "2") (pinfunction "-Ctrll_2") (pintype "passive"))
      (node (ref "U15") (pin "2") (pinfunction "-Ctrll_2") (pintype "passive"))
      (node (ref "U16") (pin "2") (pinfunction "-Ctrll_2") (pintype "passive"))
      (node (ref "U17") (pin "2") (pinfunction "-Ctrll_2") (pintype "passive"))
      (node (ref "U18") (pin "2") (pinfunction "-Ctrll_2") (pintype "passive"))
      (node (ref "U19") (pin "2") (pinfunction "-Ctrll_2") (pintype "passive"))
      (node (ref "U2") (pin "2") (pinfunction "-Ctrll_2") (pintype "passive"))
      (node (ref "U20") (pin "2") (pinfunction "-Ctrll_2") (pintype "passive"))
      (node (ref "U21") (pin "2") (pinfunction "-Ctrll_2") (pintype "passive"))
      (node (ref "U22") (pin "2") (pinfunction "-Ctrll_2") (pintype "passive"))
      (node (ref "U23") (pin "2") (pinfunction "-Ctrll_2") (pintype "passive"))
      (node (ref "U24") (pin "2") (pinfunction "-Ctrll_2") (pintype "passive"))
      (node (ref "U3") (pin "2") (pinfunction "-Ctrll_2") (pintype "passive"))
      (node (ref "U4") (pin "2") (pinfunction "-Ctrll_2") (pintype "passive"))
      (node (ref "U5") (pin "2") (pinfunction "-Ctrll_2") (pintype "passive"))
      (node (ref "U6") (pin "2") (pinfunction "-Ctrll_2") (pintype "passive"))
      (node (ref "U7") (pin "2") (pinfunction "-Ctrll_2") (pintype "passive"))
      (node (ref "U8") (pin "2") (pinfunction "-Ctrll_2") (pintype "passive"))
      (node (ref "U9") (pin "2") (pinfunction "-Ctrll_2") (pintype "passive"))
    )
  )
)
